# 2_Analog_Front-End.net
KiCad netlist of a schematic drawn in Altium Designer
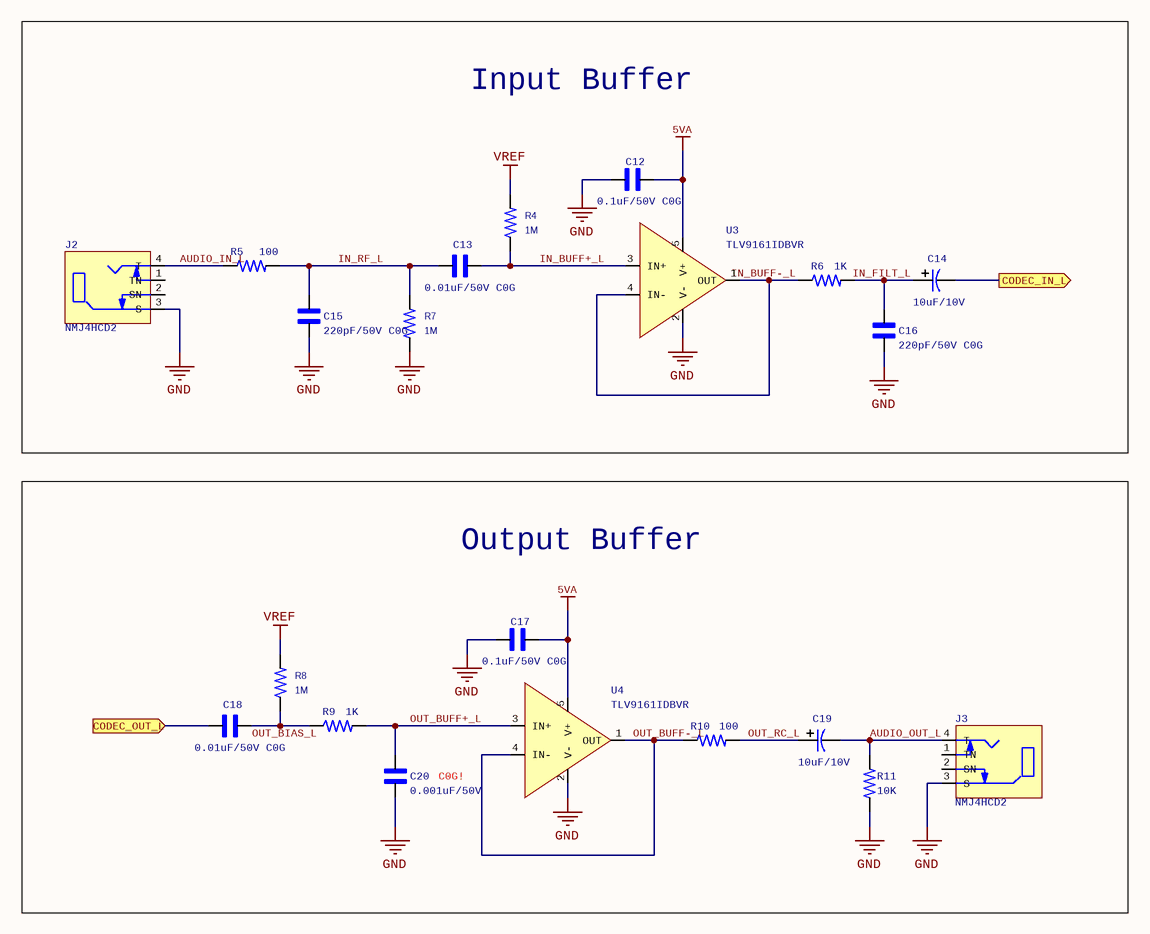
[diagram p0: [2] Analog Front-End.SchDoc]

(export (version "E")
  (design (tool "Eeschema 10.0.6"))
  (components
    (comp (ref "C12")
      (value "0.1uF/50V C0G")
      (footprint "C0603")
      (description "MLCC 0.1uF 50V C0G 10% 0603")
      (fields
        (field (name "MANUFACTURER") "TDK")
        (field (name "MANUFACTURER PART NUMBER") "C1608X5R1H104K080AA")
      )
      (libsource (lib "Capacitors") (part "C0603 0.1uF/50V"))
    )
    (comp (ref "C13")
      (value "0.01uF/50V C0G")
      (footprint "C0603")
      (description "MLCC 0.01uF 50V C0G 5% 0603")
      (fields
        (field (name "MANUFACTURER") "Murata")
        (field (name "MANUFACTURER PART NUMBER") "GRM1885C1H103JA01J")
      )
      (libsource (lib "Capacitors") (part "C0603 0.01uF/50V C0G"))
    )
    (comp (ref "C14")
      (value "10uF/10V")
      (footprint "EIA1206")
      (description "Tantalum Capacitors - Solid SMD 10V 10uF 10%")
      (fields
        (field (name "MANUFACTURER") "KEMET")
        (field (name "MANUFACTURER PART NUMBER") "T491A106K010AT")
      )
      (libsource (lib "Capacitors") (part "TANT 10UF/10V"))
    )
    (comp (ref "C15")
      (value "220pF/50V C0G")
      (footprint "C0603")
      (description "MLCC 220pF 50V C0G 5% 0603")
      (fields
        (field (name "MANUFACTURER") "KEMET")
        (field (name "MANUFACTURER PART NUMBER") "C0603C221J5GACTU")
      )
      (libsource (lib "Capacitors") (part "C0603 220pF/50V C0G"))
    )
    (comp (ref "C16")
      (value "220pF/50V C0G")
      (footprint "C0603")
      (description "MLCC 220pF 50V C0G 5% 0603")
      (fields
        (field (name "MANUFACTURER") "KEMET")
        (field (name "MANUFACTURER PART NUMBER") "C0603C221J5GACTU")
      )
      (libsource (lib "Capacitors") (part "C0603 220pF/50V C0G"))
    )
    (comp (ref "C17")
      (value "0.1uF/50V C0G")
      (footprint "C0603")
      (description "MLCC 0.1uF 50V C0G 10% 0603")
      (fields
        (field (name "MANUFACTURER") "TDK")
        (field (name "MANUFACTURER PART NUMBER") "C1608X5R1H104K080AA")
      )
      (libsource (lib "Capacitors") (part "C0603 0.1uF/50V"))
    )
    (comp (ref "C18")
      (value "0.01uF/50V C0G")
      (footprint "C0603")
      (description "MLCC 0.01uF 50V C0G 5% 0603")
      (fields
        (field (name "MANUFACTURER") "Murata")
        (field (name "MANUFACTURER PART NUMBER") "GRM1885C1H103JA01J")
      )
      (libsource (lib "Capacitors") (part "C0603 0.01uF/50V C0G"))
    )
    (comp (ref "C19")
      (value "10uF/10V")
      (footprint "EIA1206")
      (description "Tantalum Capacitors - Solid SMD 10V 10uF 10%")
      (fields
        (field (name "MANUFACTURER") "KEMET")
        (field (name "MANUFACTURER PART NUMBER") "T491A106K010AT")
      )
      (libsource (lib "Capacitors") (part "TANT 10UF/10V"))
    )
    (comp (ref "C20")
      (value "0.001uF/50V")
      (footprint "C0603")
      (description "MLCC 0.001uF 50V X5R 10% 0603")
      (fields
        (field (name "MANUFACTURER") "Samsung")
        (field (name "MANUFACTURER PART NUMBER") "CL10B102KB8NNNL")
      )
      (libsource (lib "Capacitors") (part "C0603 0.001uF/50V"))
    )
    (comp (ref "J2")
      (value "NMJ4HCD2")
      (footprint "NMJ4HCD2")
      (description "Phone Connectors 2C MONO 2-SPST NC")
      (fields (field (name "MANUFACTURER") "Neutrik"))
      (libsource (lib "") (part "TS Audio Jack 6.3mm_1"))
    )
    (comp (ref "J3")
      (value "NMJ4HCD2")
      (footprint "NMJ4HCD2")
      (description "Phone Connectors 2C MONO 2-SPST NC")
      (fields (field (name "MANUFACTURER") "Neutrik"))
      (libsource (lib "Connectors") (part "TS Audio Jack 6.3mm"))
    )
    (comp (ref "R4")
      (value "1M")
      (footprint "R0603")
      (description "RES SMD 1M OHM 1% 1/10W 0603")
      (fields
        (field (name "MANUFACTURER") "Yageo")
        (field (name "MANUFACTURER PART NUMBER") "RC0603FR-071ML")
      )
      (libsource (lib "Resistors") (part "R0603 1M"))
    )
    (comp (ref "R5")
      (value "100")
      (footprint "R0603")
      (description "RES 0603 100 OHM 1% 1/10W")
      (fields
        (field (name "MANUFACTURER") "Yageo")
        (field (name "MANUFACTURER PART NUMBER") "RC0603FR-07100RL")
      )
      (libsource (lib "Resistors") (part "R0603 100"))
    )
    (comp (ref "R6")
      (value "1K")
      (footprint "R0603")
      (description "Res Thick Film 0603 1K Ohm 1% 1/10W ±50ppm/°C Molded SMD Paper T/R")
      (fields
        (field (name "MANUFACTURER") "Yageo")
        (field (name "MANUFACTURER PART NUMBER") "RE0603FRE071KL")
      )
      (libsource (lib "Resistors") (part "R0603 1K"))
    )
    (comp (ref "R7")
      (value "1M")
      (footprint "R0603")
      (description "RES SMD 1M OHM 1% 1/10W 0603")
      (fields
        (field (name "MANUFACTURER") "Yageo")
        (field (name "MANUFACTURER PART NUMBER") "RC0603FR-071ML")
      )
      (libsource (lib "Resistors") (part "R0603 1M"))
    )
    (comp (ref "R8")
      (value "1M")
      (footprint "R0603")
      (description "RES SMD 1M OHM 1% 1/10W 0603")
      (fields
        (field (name "MANUFACTURER") "Yageo")
        (field (name "MANUFACTURER PART NUMBER") "RC0603FR-071ML")
      )
      (libsource (lib "Resistors") (part "R0603 1M"))
    )
    (comp (ref "R9")
      (value "1K")
      (footprint "R0603")
      (description "Res Thick Film 0603 1K Ohm 1% 1/10W ±50ppm/°C Molded SMD Paper T/R")
      (fields
        (field (name "MANUFACTURER") "Yageo")
        (field (name "MANUFACTURER PART NUMBER") "RE0603FRE071KL")
      )
      (libsource (lib "Resistors") (part "R0603 1K"))
    )
    (comp (ref "R10")
      (value "100")
      (footprint "R0603")
      (description "RES 0603 100 OHM 1% 1/10W")
      (fields
        (field (name "MANUFACTURER") "Yageo")
        (field (name "MANUFACTURER PART NUMBER") "RC0603FR-07100RL")
      )
      (libsource (lib "Resistors") (part "R0603 100"))
    )
    (comp (ref "R11")
      (value "10K")
      (footprint "R0603")
      (description "RES 0603 10K OHM 1% 1/10W")
      (fields
        (field (name "MANUFACTURER") "Yageo")
        (field (name "MANUFACTURER PART NUMBER") "RC0603FR-0710KP")
      )
      (libsource (lib "Resistors") (part "R0603 10K"))
    )
    (comp (ref "U3")
      (value "TLV9161IDBVR")
      (footprint "SOT23-5")
      (fields (field (name "MANUFACTURER") "Texas Instruments"))
      (libsource (lib "IC Amplifier") (part "TLV9161IDBVR"))
    )
    (comp (ref "U4")
      (value "TLV9161IDBVR")
      (footprint "SOT23-5")
      (fields (field (name "MANUFACTURER") "Texas Instruments"))
      (libsource (lib "IC Amplifier") (part "TLV9161IDBVR"))
    )
  )
  (nets
    (net (code "1") (name "/AUDIO_IN_L") (class "Default")
      (node (ref "J2") (pin "4") (pinfunction "T_4") (pintype "passive"))
      (node (ref "R5") (pin "1") (pinfunction "1_1") (pintype "passive"))
    )
    (net (code "2") (name "/AUDIO_OUT_L") (class "Default")
      (node (ref "C19") (pin "2") (pinfunction "2_2") (pintype "passive"))
      (node (ref "J3") (pin "4") (pinfunction "T_4") (pintype "passive"))
      (node (ref "R11") (pin "2") (pinfunction "2_2") (pintype "passive"))
    )
    (net (code "3") (name "/CODEC_IN_L") (class "Default")
      (node (ref "C14") (pin "2") (pinfunction "2_2") (pintype "passive"))
    )
    (net (code "4") (name "/CODEC_OUT_L") (class "Default")
      (node (ref "C18") (pin "1") (pinfunction "1_1") (pintype "passive"))
    )
    (net (code "5") (name "/IN_BUFF+_L") (class "Default")
      (node (ref "C13") (pin "2") (pinfunction "2_2") (pintype "passive"))
      (node (ref "R4") (pin "1") (pinfunction "1_1") (pintype "passive"))
      (node (ref "U3") (pin "3") (pinfunction "IN+_3") (pintype "passive"))
    )
    (net (code "6") (name "/IN_BUFF-_L") (class "Default")
      (node (ref "R6") (pin "1") (pinfunction "1_1") (pintype "passive"))
      (node (ref "U3") (pin "1") (pinfunction "OUT_1") (pintype "passive"))
      (node (ref "U3") (pin "4") (pinfunction "IN-_4") (pintype "passive"))
    )
    (net (code "7") (name "/IN_FILT_L") (class "Default")
      (node (ref "C14") (pin "1") (pinfunction "1_1") (pintype "passive"))
      (node (ref "C16") (pin "1") (pinfunction "1_1") (pintype "passive"))
      (node (ref "R6") (pin "2") (pinfunction "2_2") (pintype "passive"))
    )
    (net (code "8") (name "/IN_RF_L") (class "Default")
      (node (ref "C13") (pin "1") (pinfunction "1_1") (pintype "passive"))
      (node (ref "C15") (pin "1") (pinfunction "1_1") (pintype "passive"))
      (node (ref "R5") (pin "2") (pinfunction "2_2") (pintype "passive"))
      (node (ref "R7") (pin "2") (pinfunction "2_2") (pintype "passive"))
    )
    (net (code "9") (name "/OUT_BIAS_L") (class "Default")
      (node (ref "C18") (pin "2") (pinfunction "2_2") (pintype "passive"))
      (node (ref "R8") (pin "1") (pinfunction "1_1") (pintype "passive"))
      (node (ref "R9") (pin "1") (pinfunction "1_1") (pintype "passive"))
    )
    (net (code "10") (name "/OUT_BUFF+_L") (class "Default")
      (node (ref "C20") (pin "2") (pinfunction "2_2") (pintype "passive"))
      (node (ref "R9") (pin "2") (pinfunction "2_2") (pintype "passive"))
      (node (ref "U4") (pin "3") (pinfunction "IN+_3") (pintype "passive"))
    )
    (net (code "11") (name "/OUT_BUFF-_L") (class "Default")
      (node (ref "R10") (pin "1") (pinfunction "1_1") (pintype "passive"))
      (node (ref "U4") (pin "1") (pinfunction "OUT_1") (pintype "passive"))
      (node (ref "U4") (pin "4") (pinfunction "IN-_4") (pintype "passive"))
    )
    (net (code "12") (name "/OUT_RC_L") (class "Default")
      (node (ref "C19") (pin "1") (pinfunction "1_1") (pintype "passive"))
      (node (ref "R10") (pin "2") (pinfunction "2_2") (pintype "passive"))
    )
    (net (code "13") (name "5VA") (class "Default")
      (node (ref "C12") (pin "1") (pinfunction "1_1") (pintype "passive"))
      (node (ref "C17") (pin "1") (pinfunction "1_1") (pintype "passive"))
      (node (ref "U3") (pin "5") (pinfunction "V+_5") (pintype "passive"))
      (node (ref "U4") (pin "5") (pinfunction "V+_5") (pintype "passive"))
    )
    (net (code "14") (name "GND") (class "Default")
      (node (ref "C12") (pin "2") (pinfunction "2_2") (pintype "passive"))
      (node (ref "C15") (pin "2") (pinfunction "2_2") (pintype "passive"))
      (node (ref "C16") (pin "2") (pinfunction "2_2") (pintype "passive"))
      (node (ref "C17") (pin "2") (pinfunction "2_2") (pintype "passive"))
      (node (ref "C20") (pin "1") (pinfunction "1_1") (pintype "passive"))
      (node (ref "J2") (pin "3") (pinfunction "S_3") (pintype "passive"))
      (node (ref "J3") (pin "3") (pinfunction "S_3") (pintype "passive"))
      (node (ref "R11") (pin "1") (pinfunction "1_1") (pintype "passive"))
      (node (ref "R7") (pin "1") (pinfunction "1_1") (pintype "passive"))
      (node (ref "U3") (pin "2") (pinfunction "V-_2") (pintype "passive"))
      (node (ref "U4") (pin "2") (pinfunction "V-_2") (pintype "passive"))
    )
    (net (code "15") (name "VREF") (class "Default")
      (node (ref "R4") (pin "2") (pinfunction "2_2") (pintype "passive"))
      (node (ref "R8") (pin "2") (pinfunction "2_2") (pintype "passive"))
    )
    (net (code "16") (name "unconnected-(J2-SN-Pad2)") (class "Default")
      (node (ref "J2") (pin "2") (pinfunction "SN_2") (pintype "passive"))
    )
    (net (code "17") (name "unconnected-(J2-TN-Pad1)") (class "Default")
      (node (ref "J2") (pin "1") (pinfunction "TN_1") (pintype "passive"))
    )
    (net (code "18") (name "unconnected-(J3-SN-Pad2)") (class "Default")
      (node (ref "J3") (pin "2") (pinfunction "SN_2") (pintype "passive"))
    )
    (net (code "19") (name "unconnected-(J3-TN-Pad1)") (class "Default")
      (node (ref "J3") (pin "1") (pinfunction "TN_1") (pintype "passive"))
    )
  )
)
